# tricorder-teensy-mk-1_8.net
KiCad netlist of a schematic drawn in EAGLE
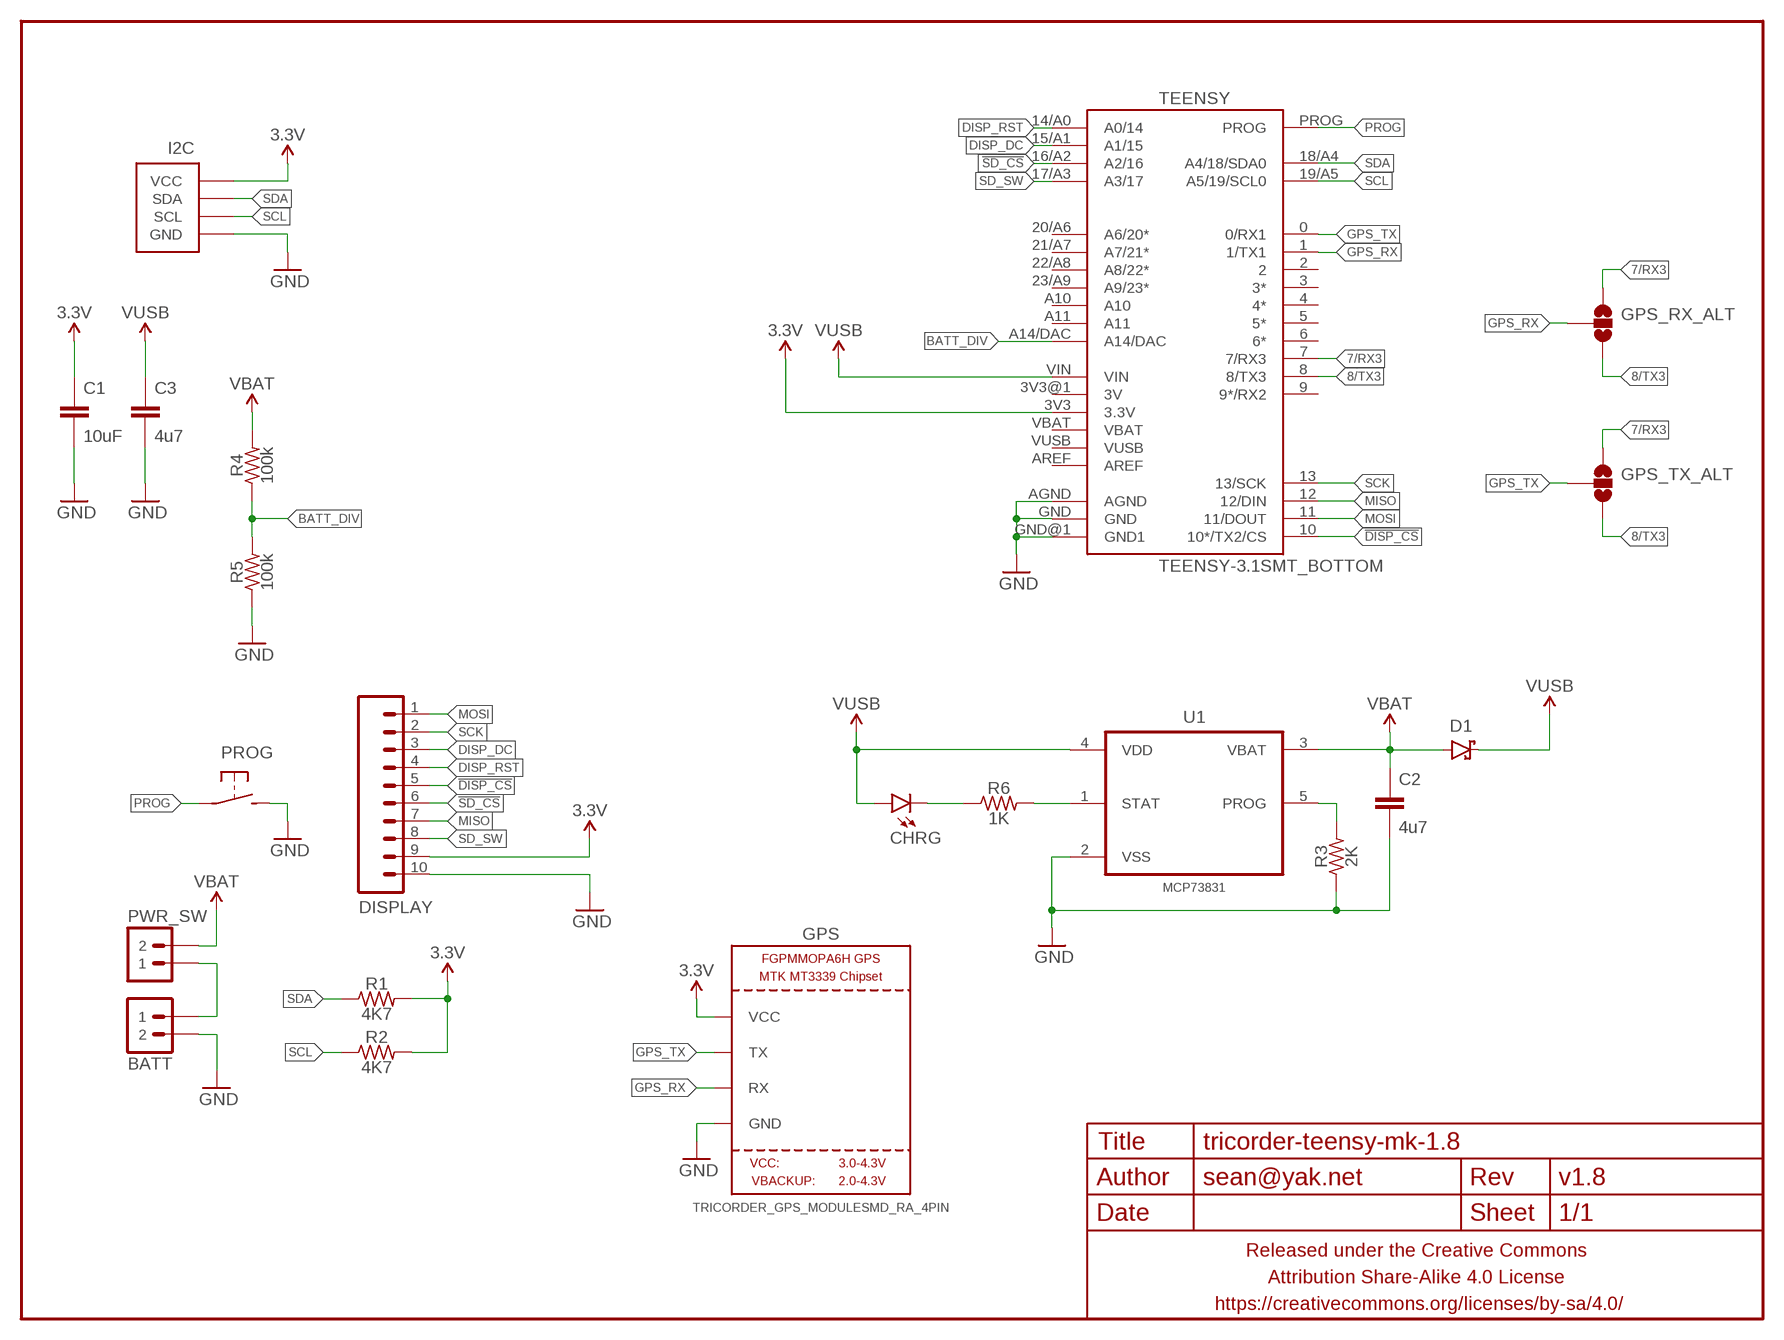
[diagram p0: schematic, sheet 1]

(export (version "E")
  (design (tool "Eeschema 10.0.6"))
  (components
    (comp (ref "BATT")
      (value "M02JST-2MM-SMT")
      (footprint "eagle-import:JST-2-SMD")
      (libsource (lib "eagle-import") (part "M02JST-2MM-SMT"))
    )
    (comp (ref "C1")
      (value "10uF")
      (footprint "eagle-import:C1210")
      (libsource (lib "eagle-import") (part "CAPACITOR-CERAMICC1210"))
    )
    (comp (ref "C2")
      (value "4u7")
      (footprint "eagle-import:C0603-TIGHTER")
      (libsource (lib "eagle-import") (part "CAPACITOR-CERAMICC0603-TIGHTER"))
    )
    (comp (ref "C3")
      (value "4u7")
      (footprint "eagle-import:C0603-TIGHTER")
      (libsource (lib "eagle-import") (part "CAPACITOR-CERAMICC0603-TIGHTER"))
    )
    (comp (ref "CHRG")
      (value "LED0603-TIGHT")
      (footprint "eagle-import:LED-0603-TIGHT")
      (libsource (lib "eagle-import") (part "LED0603-TIGHT"))
    )
    (comp (ref "D1")
      (value "DIODE-SCHOTTKYSOD123")
      (footprint "eagle-import:SOD123-SCHOTTKY")
      (libsource (lib "eagle-import") (part "DIODE-SCHOTTKYSOD123"))
    )
    (comp (ref "DISPLAY")
      (value "M10SMD_RA_2MM")
      (footprint "eagle-import:1X10_SMD_RA_MALE")
      (libsource (lib "eagle-import") (part "M10SMD_RA_2MM"))
    )
    (comp (ref "FRAME1")
      (value "FRAME-LETTERNO_PACKAGE")
      (footprint "eagle-import:DUMMY")
      (fields (field (name "DESIGNER") "sean@yak.net") (field (name "VERSION") "v1.8"))
      (libsource (lib "eagle-import") (part "FRAME-LETTERNO_PACKAGE"))
    )
    (comp (ref "GPS")
      (value "TRICORDER_GPS_MODULESMD_RA_4PIN")
      (footprint "eagle-import:TRICORDER_GPS_MODULE_RA_CONN_SMD_4PIN")
      (libsource (lib "eagle-import") (part "TRICORDER_GPS_MODULESMD_RA_4PIN"))
    )
    (comp (ref "GPS_RX_ALT")
      (value "JUMPER-PAD-3-NOFULL_BOX_SILK")
      (footprint "eagle-import:PAD-JUMPER-3-NO_YES_SILK_FULL_BOX")
      (libsource (lib "eagle-import") (part "JUMPER-PAD-3-NOFULL_BOX_SILK"))
    )
    (comp (ref "GPS_TX_ALT")
      (value "JUMPER-PAD-3-NOFULL_BOX_SILK")
      (footprint "eagle-import:PAD-JUMPER-3-NO_YES_SILK_FULL_BOX")
      (libsource (lib "eagle-import") (part "JUMPER-PAD-3-NOFULL_BOX_SILK"))
    )
    (comp (ref "I2C")
      (value "M04-I2CSMD_2MM_RA")
      (footprint "eagle-import:1X04_SMD_RA_2MM_I2C")
      (libsource (lib "eagle-import") (part "M04-I2CSMD_2MM_RA"))
    )
    (comp (ref "PROG")
      (value "SPST-NO-TACTCK-PTS840-GK")
      (footprint "eagle-import:TACTILE-SMD-CK-PTS840-GK")
      (libsource (lib "eagle-import") (part "SPST-NO-TACTCK-PTS840-GK"))
    )
    (comp (ref "PWR_SW")
      (value "M02JST-2MM-SMT")
      (footprint "eagle-import:JST-2-SMD")
      (libsource (lib "eagle-import") (part "M02JST-2MM-SMT"))
    )
    (comp (ref "R1")
      (value "4K7")
      (footprint "eagle-import:R0603-TIGHTER")
      (libsource (lib "eagle-import") (part "RESISTORR0603-TIGHTER"))
    )
    (comp (ref "R2")
      (value "4K7")
      (footprint "eagle-import:R0603-TIGHTER")
      (libsource (lib "eagle-import") (part "RESISTORR0603-TIGHTER"))
    )
    (comp (ref "R3")
      (value "2K")
      (footprint "eagle-import:R0603-TIGHTER")
      (libsource (lib "eagle-import") (part "RESISTORR0603-TIGHTER"))
    )
    (comp (ref "R4")
      (value "100k")
      (footprint "eagle-import:R0603-TIGHTER")
      (libsource (lib "eagle-import") (part "RESISTORR0603-TIGHTER"))
    )
    (comp (ref "R5")
      (value "100k")
      (footprint "eagle-import:R0603-TIGHTER")
      (libsource (lib "eagle-import") (part "RESISTORR0603-TIGHTER"))
    )
    (comp (ref "R6")
      (value "1K")
      (footprint "eagle-import:R0603-TIGHTER")
      (libsource (lib "eagle-import") (part "RESISTORR0603-TIGHTER"))
    )
    (comp (ref "TEENSY")
      (value "TEENSY-3.1SMT_BOTTOM")
      (footprint "eagle-import:TEENSY-3.1_SMT_BOTTOM")
      (libsource (lib "eagle-import") (part "TEENSY-3.1SMT_BOTTOM"))
    )
    (comp (ref "U1")
      (value "MCP73831")
      (footprint "eagle-import:SOT95P280X145-5N")
      (fields (field (name "MPN") "MCP73831T-2ACI/OT"))
      (libsource (lib "eagle-import") (part "MCP73831T-2ACI/OT"))
    )
  )
  (nets
    (net (code "1") (name "/~{DISP_CS}") (class "Default")
      (node (ref "DISPLAY") (pin "5") (pinfunction "5_5") (pintype "passive"))
      (node (ref "TEENSY") (pin "10") (pinfunction "10*/TX2/CS_10") (pintype "bidirectional"))
    )
    (net (code "2") (name "/~{SD_CS}") (class "Default")
      (node (ref "DISPLAY") (pin "6") (pinfunction "6_6") (pintype "passive"))
      (node (ref "TEENSY") (pin "16/A2") (pinfunction "A2/16_16/A2") (pintype "bidirectional"))
    )
    (net (code "3") (name "3.3V") (class "Default")
      (node (ref "C1") (pin "1") (pinfunction "1_1") (pintype "passive"))
      (node (ref "DISPLAY") (pin "9") (pinfunction "9_9") (pintype "passive"))
      (node (ref "GPS") (pin "VCC") (pinfunction "VCC_VCC") (pintype "bidirectional"))
      (node (ref "I2C") (pin "VCC") (pinfunction "VCC_VCC") (pintype "bidirectional"))
      (node (ref "R1") (pin "2") (pinfunction "2_2") (pintype "passive"))
      (node (ref "R2") (pin "2") (pinfunction "2_2") (pintype "passive"))
      (node (ref "TEENSY") (pin "3V3") (pinfunction "3.3V_3V3") (pintype "bidirectional"))
    )
    (net (code "4") (name "7{slash}RX3") (class "Default")
      (node (ref "GPS_RX_ALT") (pin "1") (pinfunction "1_1") (pintype "passive"))
      (node (ref "GPS_TX_ALT") (pin "1") (pinfunction "1_1") (pintype "passive"))
      (node (ref "TEENSY") (pin "7") (pinfunction "7/RX3_7") (pintype "bidirectional"))
    )
    (net (code "5") (name "8{slash}TX3") (class "Default")
      (node (ref "GPS_RX_ALT") (pin "3") (pinfunction "3_3") (pintype "passive"))
      (node (ref "GPS_TX_ALT") (pin "3") (pinfunction "3_3") (pintype "passive"))
      (node (ref "TEENSY") (pin "8") (pinfunction "8/TX3_8") (pintype "bidirectional"))
    )
    (net (code "6") (name "BATT_DIV") (class "Default")
      (node (ref "R4") (pin "1") (pinfunction "1_1") (pintype "passive"))
      (node (ref "R5") (pin "2") (pinfunction "2_2") (pintype "passive"))
      (node (ref "TEENSY") (pin "A14/DAC") (pinfunction "A14/DAC_A14/DAC") (pintype "bidirectional"))
    )
    (net (code "7") (name "DISP_DC") (class "Default")
      (node (ref "DISPLAY") (pin "3") (pinfunction "3_3") (pintype "passive"))
      (node (ref "TEENSY") (pin "15/A1") (pinfunction "A1/15_15/A1") (pintype "bidirectional"))
    )
    (net (code "8") (name "DISP_RST") (class "Default")
      (node (ref "DISPLAY") (pin "4") (pinfunction "4_4") (pintype "passive"))
      (node (ref "TEENSY") (pin "14/A0") (pinfunction "A0/14_14/A0") (pintype "bidirectional"))
    )
    (net (code "9") (name "GND") (class "Default")
      (node (ref "BATT") (pin "1") (pinfunction "2_1") (pintype "passive"))
      (node (ref "C1") (pin "2") (pinfunction "2_2") (pintype "passive"))
      (node (ref "C2") (pin "2") (pinfunction "2_2") (pintype "passive"))
      (node (ref "C3") (pin "2") (pinfunction "2_2") (pintype "passive"))
      (node (ref "DISPLAY") (pin "10") (pinfunction "10_10") (pintype "passive"))
      (node (ref "GPS") (pin "GND") (pinfunction "GND_GND") (pintype "bidirectional"))
      (node (ref "I2C") (pin "GND") (pinfunction "GND_GND") (pintype "bidirectional"))
      (node (ref "PROG") (pin "3") (pinfunction "2_3") (pintype "passive"))
      (node (ref "PROG") (pin "4") (pinfunction "2_4") (pintype "passive"))
      (node (ref "R3") (pin "1") (pinfunction "1_1") (pintype "passive"))
      (node (ref "R5") (pin "1") (pinfunction "1_1") (pintype "passive"))
      (node (ref "TEENSY") (pin "AGND") (pinfunction "AGND_AGND") (pintype "bidirectional"))
      (node (ref "TEENSY") (pin "GND") (pinfunction "GND_GND") (pintype "bidirectional"))
      (node (ref "TEENSY") (pin "GND@1") (pinfunction "GND1_GND@1") (pintype "bidirectional"))
      (node (ref "U1") (pin "2") (pinfunction "VSS_2") (pintype "power_in"))
    )
    (net (code "10") (name "GPS_RX") (class "Default")
      (node (ref "GPS") (pin "RX") (pinfunction "RX_RX") (pintype "bidirectional"))
      (node (ref "GPS_RX_ALT") (pin "2") (pinfunction "2_2") (pintype "passive"))
      (node (ref "TEENSY") (pin "1") (pinfunction "1/TX1_1") (pintype "bidirectional"))
    )
    (net (code "11") (name "GPS_TX") (class "Default")
      (node (ref "GPS") (pin "TX") (pinfunction "TX_TX") (pintype "bidirectional"))
      (node (ref "GPS_TX_ALT") (pin "2") (pinfunction "2_2") (pintype "passive"))
      (node (ref "TEENSY") (pin "0") (pinfunction "0/RX1_0") (pintype "bidirectional"))
    )
    (net (code "12") (name "MISO") (class "Default")
      (node (ref "DISPLAY") (pin "7") (pinfunction "7_7") (pintype "passive"))
      (node (ref "TEENSY") (pin "12") (pinfunction "12/DIN_12") (pintype "bidirectional"))
    )
    (net (code "13") (name "MOSI") (class "Default")
      (node (ref "DISPLAY") (pin "1") (pinfunction "1_1") (pintype "passive"))
      (node (ref "TEENSY") (pin "11") (pinfunction "11/DOUT_11") (pintype "bidirectional"))
    )
    (net (code "14") (name "Net-(BATT-1)") (class "Default")
      (node (ref "BATT") (pin "2") (pinfunction "1_2") (pintype "passive"))
      (node (ref "PWR_SW") (pin "2") (pinfunction "1_2") (pintype "passive"))
    )
    (net (code "15") (name "Net-(CHRG-PadC)") (class "Default")
      (node (ref "CHRG") (pin "C") (pinfunction "C_C") (pintype "passive"))
      (node (ref "R6") (pin "1") (pinfunction "1_1") (pintype "passive"))
    )
    (net (code "16") (name "Net-(U1-PROG)") (class "Default")
      (node (ref "R3") (pin "2") (pinfunction "2_2") (pintype "passive"))
      (node (ref "U1") (pin "5") (pinfunction "PROG_5") (pintype "input"))
    )
    (net (code "17") (name "Net-(U1-STAT)") (class "Default")
      (node (ref "R6") (pin "2") (pinfunction "2_2") (pintype "passive"))
      (node (ref "U1") (pin "1") (pinfunction "STAT_1") (pintype "output"))
    )
    (net (code "18") (name "PROG") (class "Default")
      (node (ref "PROG") (pin "1") (pinfunction "1_1") (pintype "passive"))
      (node (ref "PROG") (pin "2") (pinfunction "1_2") (pintype "passive"))
      (node (ref "TEENSY") (pin "PROG") (pinfunction "PROG_PROG") (pintype "bidirectional"))
    )
    (net (code "19") (name "SCK") (class "Default")
      (node (ref "DISPLAY") (pin "2") (pinfunction "2_2") (pintype "passive"))
      (node (ref "TEENSY") (pin "13") (pinfunction "13/SCK_13") (pintype "bidirectional"))
    )
    (net (code "20") (name "SCL") (class "Default")
      (node (ref "I2C") (pin "SCL") (pinfunction "SCL_SCL") (pintype "bidirectional"))
      (node (ref "R2") (pin "1") (pinfunction "1_1") (pintype "passive"))
      (node (ref "TEENSY") (pin "19/A5") (pinfunction "A5/19/SCL0_19/A5") (pintype "bidirectional"))
    )
    (net (code "21") (name "SDA") (class "Default")
      (node (ref "I2C") (pin "SDA") (pinfunction "SDA_SDA") (pintype "bidirectional"))
      (node (ref "R1") (pin "1") (pinfunction "1_1") (pintype "passive"))
      (node (ref "TEENSY") (pin "18/A4") (pinfunction "A4/18/SDA0_18/A4") (pintype "bidirectional"))
    )
    (net (code "22") (name "SD_SW") (class "Default")
      (node (ref "DISPLAY") (pin "8") (pinfunction "8_8") (pintype "passive"))
      (node (ref "TEENSY") (pin "17/A3") (pinfunction "A3/17_17/A3") (pintype "bidirectional"))
    )
    (net (code "23") (name "VBAT") (class "Default")
      (node (ref "C2") (pin "1") (pinfunction "1_1") (pintype "passive"))
      (node (ref "D1") (pin "A") (pinfunction "A_A") (pintype "passive"))
      (node (ref "PWR_SW") (pin "1") (pinfunction "2_1") (pintype "passive"))
      (node (ref "R4") (pin "2") (pinfunction "2_2") (pintype "passive"))
      (node (ref "U1") (pin "3") (pinfunction "VBAT_3") (pintype "output"))
    )
    (net (code "24") (name "VUSB") (class "Default")
      (node (ref "C3") (pin "1") (pinfunction "1_1") (pintype "passive"))
      (node (ref "CHRG") (pin "A") (pinfunction "A_A") (pintype "passive"))
      (node (ref "D1") (pin "C") (pinfunction "C_C") (pintype "passive"))
      (node (ref "TEENSY") (pin "VIN") (pinfunction "VIN_VIN") (pintype "bidirectional"))
      (node (ref "U1") (pin "4") (pinfunction "VDD_4") (pintype "power_in"))
    )
    (net (code "25") (name "unconnected-(TEENSY-3*-Pad3)") (class "Default")
      (node (ref "TEENSY") (pin "3") (pinfunction "3*_3") (pintype "bidirectional"))
    )
    (net (code "26") (name "unconnected-(TEENSY-3V-Pad3V3@1)") (class "Default")
      (node (ref "TEENSY") (pin "3V3@1") (pinfunction "3V_3V3@1") (pintype "bidirectional"))
    )
    (net (code "27") (name "unconnected-(TEENSY-4*-Pad4)") (class "Default")
      (node (ref "TEENSY") (pin "4") (pinfunction "4*_4") (pintype "bidirectional"))
    )
    (net (code "28") (name "unconnected-(TEENSY-5*-Pad5)") (class "Default")
      (node (ref "TEENSY") (pin "5") (pinfunction "5*_5") (pintype "bidirectional"))
    )
    (net (code "29") (name "unconnected-(TEENSY-6*-Pad6)") (class "Default")
      (node (ref "TEENSY") (pin "6") (pinfunction "6*_6") (pintype "bidirectional"))
    )
    (net (code "30") (name "unconnected-(TEENSY-9*{slash}RX2-Pad9)") (class "Default")
      (node (ref "TEENSY") (pin "9") (pinfunction "9*/RX2_9") (pintype "bidirectional"))
    )
    (net (code "31") (name "unconnected-(TEENSY-A6{slash}20*-Pad20{slash}A6)") (class "Default")
      (node (ref "TEENSY") (pin "20/A6") (pinfunction "A6/20*_20/A6") (pintype "bidirectional"))
    )
    (net (code "32") (name "unconnected-(TEENSY-A7{slash}21*-Pad21{slash}A7)") (class "Default")
      (node (ref "TEENSY") (pin "21/A7") (pinfunction "A7/21*_21/A7") (pintype "bidirectional"))
    )
    (net (code "33") (name "unconnected-(TEENSY-A8{slash}22*-Pad22{slash}A8)") (class "Default")
      (node (ref "TEENSY") (pin "22/A8") (pinfunction "A8/22*_22/A8") (pintype "bidirectional"))
    )
    (net (code "34") (name "unconnected-(TEENSY-A9{slash}23*-Pad23{slash}A9)") (class "Default")
      (node (ref "TEENSY") (pin "23/A9") (pinfunction "A9/23*_23/A9") (pintype "bidirectional"))
    )
    (net (code "35") (name "unconnected-(TEENSY-Pad2)") (class "Default")
      (node (ref "TEENSY") (pin "2") (pinfunction "2_2") (pintype "bidirectional"))
    )
    (net (code "36") (name "unconnected-(TEENSY-PadA10)") (class "Default")
      (node (ref "TEENSY") (pin "A10") (pinfunction "A10_A10") (pintype "bidirectional"))
    )
    (net (code "37") (name "unconnected-(TEENSY-PadA11)") (class "Default")
      (node (ref "TEENSY") (pin "A11") (pinfunction "A11_A11") (pintype "bidirectional"))
    )
    (net (code "38") (name "unconnected-(TEENSY-PadAREF)") (class "Default")
      (node (ref "TEENSY") (pin "AREF") (pinfunction "AREF_AREF") (pintype "bidirectional"))
    )
    (net (code "39") (name "unconnected-(TEENSY-PadVBAT)") (class "Default")
      (node (ref "TEENSY") (pin "VBAT") (pinfunction "VBAT_VBAT") (pintype "bidirectional"))
    )
    (net (code "40") (name "unconnected-(TEENSY-PadVUSB)") (class "Default")
      (node (ref "TEENSY") (pin "VUSB") (pinfunction "VUSB_VUSB") (pintype "bidirectional"))
    )
  )
)
